# 10_Mains_Input.net
KiCad netlist of a schematic drawn in Altium Designer
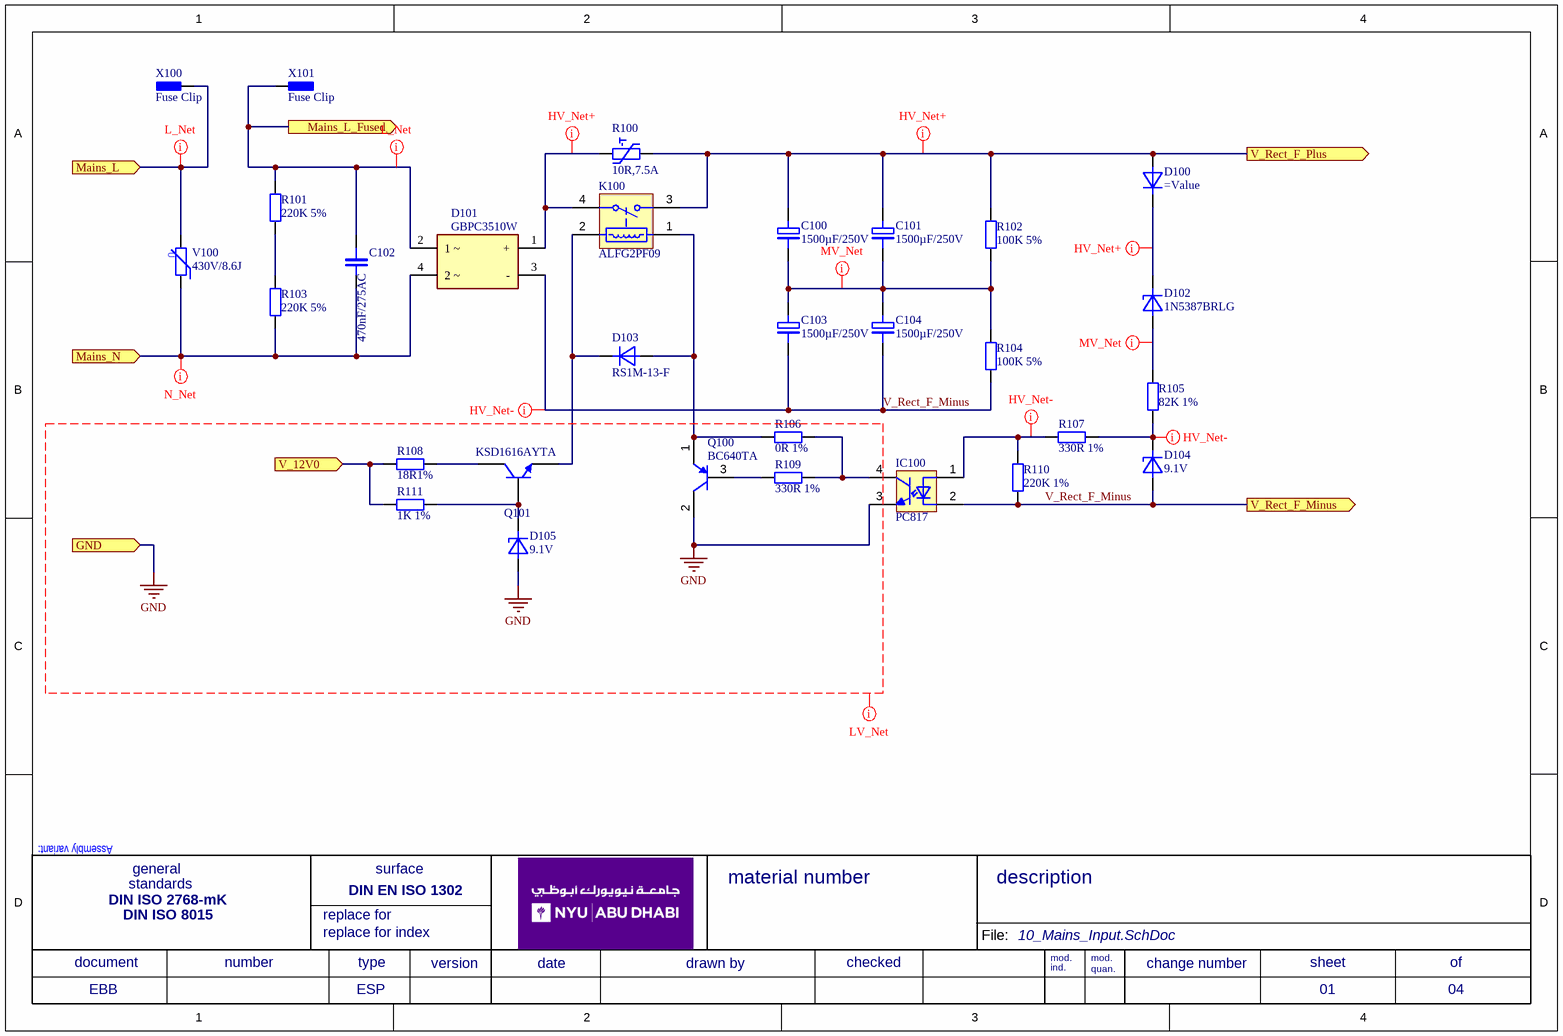
[diagram p0: 10_Mains_Input.SchDoc]

(export (version "E")
  (design (tool "Eeschema 10.0.6"))
  (components
    (comp (ref "C100")
      (value "1500µF/250V")
      (footprint "CAPACITOR-ELKO-400V-RM10-35x50")
      (description "1500µF, 250V, Radial, 3000HRS")
      (fields (field (name "MANUFACTURER") "Cornell") (field (name "CREATED BY") "Hamad"))
      (libsource (lib "Amjad_Components") (part "ECAP"))
    )
    (comp (ref "C101")
      (value "1500µF/250V")
      (footprint "CAPACITOR-ELKO-400V-RM10-35x50")
      (description "1500µF, 250V, Radial, 3000HRS")
      (fields (field (name "MANUFACTURER") "Cornell") (field (name "CREATED BY") "Hamad"))
      (libsource (lib "Amjad_Components") (part "ECAP"))
    )
    (comp (ref "C102")
      (value "470nF/275AC")
      (footprint "CP22.5x10x26.5")
      (description "X2 Capacitor, 275VAC, l=26.5, w=8.5, h=16.5, pitch=22.5mm, 20%")
      (fields (field (name "MANUFACTURER") "Kemet") (field (name "CREATED BY") "Hamad"))
      (libsource (lib "Amjad_Components") (part "Capacitor"))
    )
    (comp (ref "C103")
      (value "1500µF/250V")
      (footprint "CAPACITOR-ELKO-400V-RM10-35x50")
      (description "1500µF, 250V, Radial, 3000HRS")
      (fields (field (name "MANUFACTURER") "Cornell") (field (name "CREATED BY") "Hamad"))
      (libsource (lib "Amjad_Components") (part "ECAP"))
    )
    (comp (ref "C104")
      (value "1500µF/250V")
      (footprint "CAPACITOR-ELKO-400V-RM10-35x50")
      (description "1500µF, 250V, Radial, 3000HRS")
      (fields (field (name "MANUFACTURER") "Cornell") (field (name "CREATED BY") "Hamad"))
      (libsource (lib "Amjad_Components") (part "ECAP"))
    )
    (comp (ref "D100")
      (value "~")
      (footprint "SMA")
      (description "1KV,1A,500ns, SMA")
      (fields (field (name "MANUFACTURER") "Diodes") (field (name "CREATED BY") "HamadA"))
      (libsource (lib "Amjad_Components") (part "Diode"))
    )
    (comp (ref "D101")
      (value "GBPC3510W")
      (footprint "GBPC3510W")
      (description "Rectififer bridge 35A 100V")
      (fields (field (name "MANUFACTURER") "Taiwan Semi") (field (name "CREATED BY") "HamadA"))
      (libsource (lib "Amjad_Components") (part "GBPC3510W"))
    )
    (comp (ref "D102")
      (value "1N5387BRLG")
      (footprint "DO-201AD")
      (description "Zener, 190V, 5%, 500nA@144V, Axial")
      (fields (field (name "MANUFACTURER") "On Semi") (field (name "CREATED BY") "HamadA"))
      (libsource (lib "Amjad_Components") (part "ZenerDiode"))
    )
    (comp (ref "D103")
      (value "RS1M-13-F")
      (footprint "SMA")
      (description "1KV,1A,500ns, SMA")
      (fields (field (name "MANUFACTURER") "Diodes") (field (name "CREATED BY") "HamadA"))
      (libsource (lib "Amjad_Components") (part "Diode"))
    )
    (comp (ref "D104")
      (value "9.1V")
      (footprint "DO-201AD")
      (description "Zener, 9.1V, 5%,0.5Watt, Axial")
      (fields (field (name "MANUFACTURER") "NXP") (field (name "CREATED BY") "HamadA"))
      (libsource (lib "Amjad_Components") (part "ZenerDiode"))
    )
    (comp (ref "D105")
      (value "9.1V")
      (footprint "DO-201AD")
      (description "Zener, 9.1V, 5%,0.5Watt, Axial")
      (fields (field (name "MANUFACTURER") "NXP") (field (name "CREATED BY") "HamadA"))
      (libsource (lib "Amjad_Components") (part "ZenerDiode"))
    )
    (comp (ref "IC100")
      (value "PC817")
      (footprint "DIP04")
      (description "Optocoupler, 1CH, DIP.4, 5KV")
      (fields (field (name "MANUFACTURER") "UTC,Sharp"))
      (libsource (lib "Amjad_Components") (part "Optocoupler"))
    )
    (comp (ref "K100")
      (value "ALFG2PF09")
      (footprint "ALFG2PF09")
      (description "General Purpose Relay SPST-NO (1 Form A) 9VDC Coil Through Hole")
      (fields (field (name "MANUFACTURER") "Panasonic") (field (name "CREATED BY") "Hamad"))
      (libsource (lib "Amjad_Components") (part "ALFG2PF09"))
    )
    (comp (ref "Q100")
      (value "BC640TA")
      (footprint "TO-92")
      (description "80V, 1A, 250mW, 100MHz,TO-92")
      (fields
        (field (name "MANUFACTURER") "On Semi")
        (field (name "ALTERNATIVE PART") "yes")
        (field (name "CREATED BY") "HamadA")
      )
      (libsource (lib "Amjad_Components") (part "Q_PNP_ECB"))
    )
    (comp (ref "Q101")
      (value "KSD1616AYTA")
      (footprint "TO-92")
      (description "60V, 1A, 250mW, 160MHz, TO-92")
      (fields
        (field (name "MANUFACTURER") "On Semi")
        (field (name "ALTERNATIVE PART") "yes")
        (field (name "CREATED BY") "HamadA")
      )
      (libsource (lib "Amjad_Components") (part "Q_NPN"))
    )
    (comp (ref "R100")
      (value "10R,7.5A")
      (footprint "NTC_D10_P7.5")
      (description "Inrush Current Limiter 10 Ohms ±20% 7.5 A 0.827\" (21.00mm)")
      (fields (field (name "MANUFACTURER") "Epcos") (field (name "CREATED BY") "HamadA"))
      (libsource (lib "Amjad_Components") (part "NTC"))
    )
    (comp (ref "R101")
      (value "220K 5%")
      (footprint "EIA1206")
      (description "Chip Resistor 1206")
      (fields (field (name "MANUFACTURER") "Vishay") (field (name "CREATED BY") "HamadA"))
      (libsource (lib "Amjad_Components") (part "R_EU"))
    )
    (comp (ref "R102")
      (value "100K 5%")
      (footprint "RES-RM20-RSF2W")
      (description "Metal Oxide Film, 2W, 51000ohm, 350V, 5% +/-Tol, 350ppm/Ce")
      (fields (field (name "MANUFACTURER") "Panasonic") (field (name "CREATED BY") "HamadA"))
      (libsource (lib "Amjad_Components") (part "R_EU"))
    )
    (comp (ref "R103")
      (value "220K 5%")
      (footprint "EIA1206")
      (description "Chip Resistor 1206")
      (fields (field (name "MANUFACTURER") "Vishay") (field (name "CREATED BY") "HamadA"))
      (libsource (lib "Amjad_Components") (part "R_EU"))
    )
    (comp (ref "R104")
      (value "100K 5%")
      (footprint "RES-RM20-RSF2W")
      (description "Metal Oxide Film, 2W, 51000ohm, 350V, 5% +/-Tol, 350ppm/Ce")
      (fields (field (name "MANUFACTURER") "Panasonic") (field (name "CREATED BY") "HamadA"))
      (libsource (lib "Amjad_Components") (part "R_EU"))
    )
    (comp (ref "R105")
      (value "82K 1%")
      (footprint "EIA1206")
      (description "Chip Resistor 1206")
      (fields (field (name "MANUFACTURER") "open source") (field (name "CREATED BY") "HamadA"))
      (libsource (lib "Amjad_Components") (part "R_EU"))
    )
    (comp (ref "R106")
      (value "0R 1%")
      (footprint "EIA0603")
      (description "Chip Resistor 0603")
      (fields (field (name "MANUFACTURER") "open source") (field (name "CREATED BY") "HamadA"))
      (libsource (lib "") (part "R_EU_1"))
    )
    (comp (ref "R107")
      (value "330R 1%")
      (footprint "EIA0603")
      (description "Chip Resistor 0603")
      (fields (field (name "MANUFACTURER") "open source") (field (name "CREATED BY") "HamadA"))
      (libsource (lib "") (part "R_EU_2"))
    )
    (comp (ref "R108")
      (value "18R1%")
      (footprint "EIA1206")
      (description "Chip Resistor 1206")
      (fields (field (name "MANUFACTURER") "open source") (field (name "CREATED BY") "HamadA"))
      (libsource (lib "") (part "R_EU_1"))
    )
    (comp (ref "R109")
      (value "330R 1%")
      (footprint "EIA0603")
      (description "Chip Resistor 0603")
      (fields (field (name "MANUFACTURER") "open source") (field (name "CREATED BY") "HamadA"))
      (libsource (lib "") (part "R_EU_1"))
    )
    (comp (ref "R110")
      (value "220K 1%")
      (footprint "EIA0603")
      (description "Chip Resistor 0603")
      (fields (field (name "MANUFACTURER") "open source") (field (name "CREATED BY") "HamadA"))
      (libsource (lib "Amjad_Components") (part "R_EU"))
    )
    (comp (ref "R111")
      (value "1K 1%")
      (footprint "EIA1206")
      (description "Chip Resistor 1206")
      (fields (field (name "MANUFACTURER") "open source") (field (name "CREATED BY") "HamadA"))
      (libsource (lib "") (part "R_EU_1"))
    )
    (comp (ref "V100")
      (value "430V/8.6J")
      (footprint "EPCOS_B72205S0271K101")
      (description "430 V 400 A Varistor 1 Circuit Through Hole Disc 5mm")
      (fields (field (name "MANUFACTURER") "EPCOS") (field (name "CREATED BY") "Hamad"))
      (libsource (lib "Amjad_Components") (part "Varistor"))
    )
    (comp (ref "X100")
      (value "Fuse Clip")
      (footprint "Fuse_Clip_01020071Z")
      (description "Fuse Clip, 1/4\" Fuses, Littlefuse, THT")
      (fields (field (name "MANUFACTURER") "LittleFuse") (field (name "CREATED BY") "Hamad"))
      (libsource (lib "Amjad_Components") (part "X01"))
    )
    (comp (ref "X101")
      (value "Fuse Clip")
      (footprint "Fuse_Clip_01020071Z")
      (description "Fuse Clip, 1/4\" Fuses, Littlefuse, THT")
      (fields (field (name "MANUFACTURER") "LittleFuse") (field (name "CREATED BY") "Hamad"))
      (libsource (lib "Amjad_Components") (part "X01"))
    )
  )
  (nets
    (net (code "1") (name "/Mains_L") (class "Default")
      (node (ref "V100") (pin "2") (pintype "passive"))
      (node (ref "X100") (pin "1") (pintype "passive"))
    )
    (net (code "2") (name "/Mains_L_Fused") (class "Default")
      (node (ref "C102") (pin "2") (pintype "passive"))
      (node (ref "D101") (pin "2") (pinfunction "1_~_2") (pintype "passive"))
      (node (ref "R101") (pin "2") (pinfunction "2_2") (pintype "passive"))
      (node (ref "X101") (pin "1") (pintype "passive"))
    )
    (net (code "3") (name "/Mains_N") (class "Default")
      (node (ref "C102") (pin "1") (pintype "passive"))
      (node (ref "D101") (pin "4") (pinfunction "2_~_4") (pintype "passive"))
      (node (ref "R103") (pin "1") (pinfunction "1_1") (pintype "passive"))
      (node (ref "V100") (pin "1") (pintype "passive"))
    )
    (net (code "4") (name "/V_12V0") (class "Default")
      (node (ref "R108") (pin "2") (pinfunction "2_2") (pintype "passive"))
      (node (ref "R111") (pin "2") (pinfunction "2_2") (pintype "passive"))
    )
    (net (code "5") (name "/V_Rect_F_Minus") (class "Default")
      (node (ref "C103") (pin "2") (pintype "passive"))
      (node (ref "C104") (pin "2") (pintype "passive"))
      (node (ref "D101") (pin "3") (pinfunction "-_3") (pintype "passive"))
      (node (ref "D104") (pin "A") (pintype "passive"))
      (node (ref "IC100") (pin "2") (pintype "passive"))
      (node (ref "R104") (pin "1") (pinfunction "1_1") (pintype "passive"))
      (node (ref "R110") (pin "1") (pinfunction "1_1") (pintype "passive"))
    )
    (net (code "6") (name "/V_Rect_F_Plus") (class "Default")
      (node (ref "C100") (pin "1") (pintype "passive"))
      (node (ref "C101") (pin "1") (pintype "passive"))
      (node (ref "D100") (pin "A") (pintype "passive"))
      (node (ref "K100") (pin "3") (pinfunction "NO_3") (pintype "passive"))
      (node (ref "R100") (pin "2") (pintype "passive"))
      (node (ref "R102") (pin "2") (pinfunction "2_2") (pintype "passive"))
    )
    (net (code "7") (name "GND") (class "Default")
      (node (ref "D105") (pin "A") (pintype "passive"))
      (node (ref "IC100") (pin "3") (pintype "passive"))
      (node (ref "Q100") (pin "2") (pinfunction "C_2") (pintype "passive"))
    )
    (net (code "8") (name "Net-(C100-Pad2)") (class "Default")
      (node (ref "C100") (pin "2") (pintype "passive"))
      (node (ref "C101") (pin "2") (pintype "passive"))
      (node (ref "C103") (pin "1") (pintype "passive"))
      (node (ref "C104") (pin "1") (pintype "passive"))
      (node (ref "R102") (pin "1") (pinfunction "1_1") (pintype "passive"))
      (node (ref "R104") (pin "2") (pinfunction "2_2") (pintype "passive"))
    )
    (net (code "9") (name "Net-(D100-PadK)") (class "Default")
      (node (ref "D100") (pin "K") (pintype "passive"))
      (node (ref "D102") (pin "K") (pintype "passive"))
    )
    (net (code "10") (name "Net-(D101-+)") (class "Default")
      (node (ref "D101") (pin "1") (pinfunction "+_1") (pintype "passive"))
      (node (ref "K100") (pin "4") (pinfunction "COM_4") (pintype "passive"))
      (node (ref "R100") (pin "1") (pintype "passive"))
    )
    (net (code "11") (name "Net-(D102-PadA)") (class "Default")
      (node (ref "D102") (pin "A") (pintype "passive"))
      (node (ref "R105") (pin "2") (pinfunction "2_2") (pintype "passive"))
    )
    (net (code "12") (name "Net-(D104-PadK)") (class "Default")
      (node (ref "D104") (pin "K") (pintype "passive"))
      (node (ref "R105") (pin "1") (pinfunction "1_1") (pintype "passive"))
      (node (ref "R107") (pin "2") (pinfunction "2_2") (pintype "passive"))
    )
    (net (code "13") (name "Net-(IC100-Pad1)") (class "Default")
      (node (ref "IC100") (pin "1") (pintype "passive"))
      (node (ref "R107") (pin "1") (pinfunction "1_1") (pintype "passive"))
      (node (ref "R110") (pin "2") (pinfunction "2_2") (pintype "passive"))
    )
    (net (code "14") (name "Net-(IC100-Pad4)") (class "Default")
      (node (ref "IC100") (pin "4") (pintype "passive"))
      (node (ref "R106") (pin "1") (pinfunction "1_1") (pintype "passive"))
      (node (ref "R109") (pin "1") (pinfunction "1_1") (pintype "passive"))
    )
    (net (code "15") (name "Net-(Q100-B)") (class "Default")
      (node (ref "Q100") (pin "3") (pinfunction "B_3") (pintype "passive"))
      (node (ref "R109") (pin "2") (pinfunction "2_2") (pintype "passive"))
    )
    (net (code "16") (name "Net-(Q100-E)") (class "Default")
      (node (ref "D103") (pin "A") (pintype "passive"))
      (node (ref "K100") (pin "1") (pinfunction "1_1") (pintype "passive"))
      (node (ref "Q100") (pin "1") (pinfunction "E_1") (pintype "passive"))
      (node (ref "R106") (pin "2") (pinfunction "2_2") (pintype "passive"))
    )
    (net (code "17") (name "Net-(Q101-B)") (class "Default")
      (node (ref "D105") (pin "K") (pintype "passive"))
      (node (ref "Q101") (pin "3") (pinfunction "B_3") (pintype "passive"))
      (node (ref "R111") (pin "1") (pinfunction "1_1") (pintype "passive"))
    )
    (net (code "18") (name "Net-(Q101-C)") (class "Default")
      (node (ref "Q101") (pin "2") (pinfunction "C_2") (pintype "passive"))
      (node (ref "R108") (pin "1") (pinfunction "1_1") (pintype "passive"))
    )
    (net (code "19") (name "Net-(Q101-E)") (class "Default")
      (node (ref "D103") (pin "K") (pintype "passive"))
      (node (ref "K100") (pin "2") (pinfunction "2_2") (pintype "passive"))
      (node (ref "Q101") (pin "1") (pinfunction "E_1") (pintype "passive"))
    )
    (net (code "20") (name "Net-(R101-Pad1)") (class "Default")
      (node (ref "R101") (pin "1") (pinfunction "1_1") (pintype "passive"))
      (node (ref "R103") (pin "2") (pinfunction "2_2") (pintype "passive"))
    )
  )
)
